# working.net
KiCad netlist of a schematic drawn in EAGLE
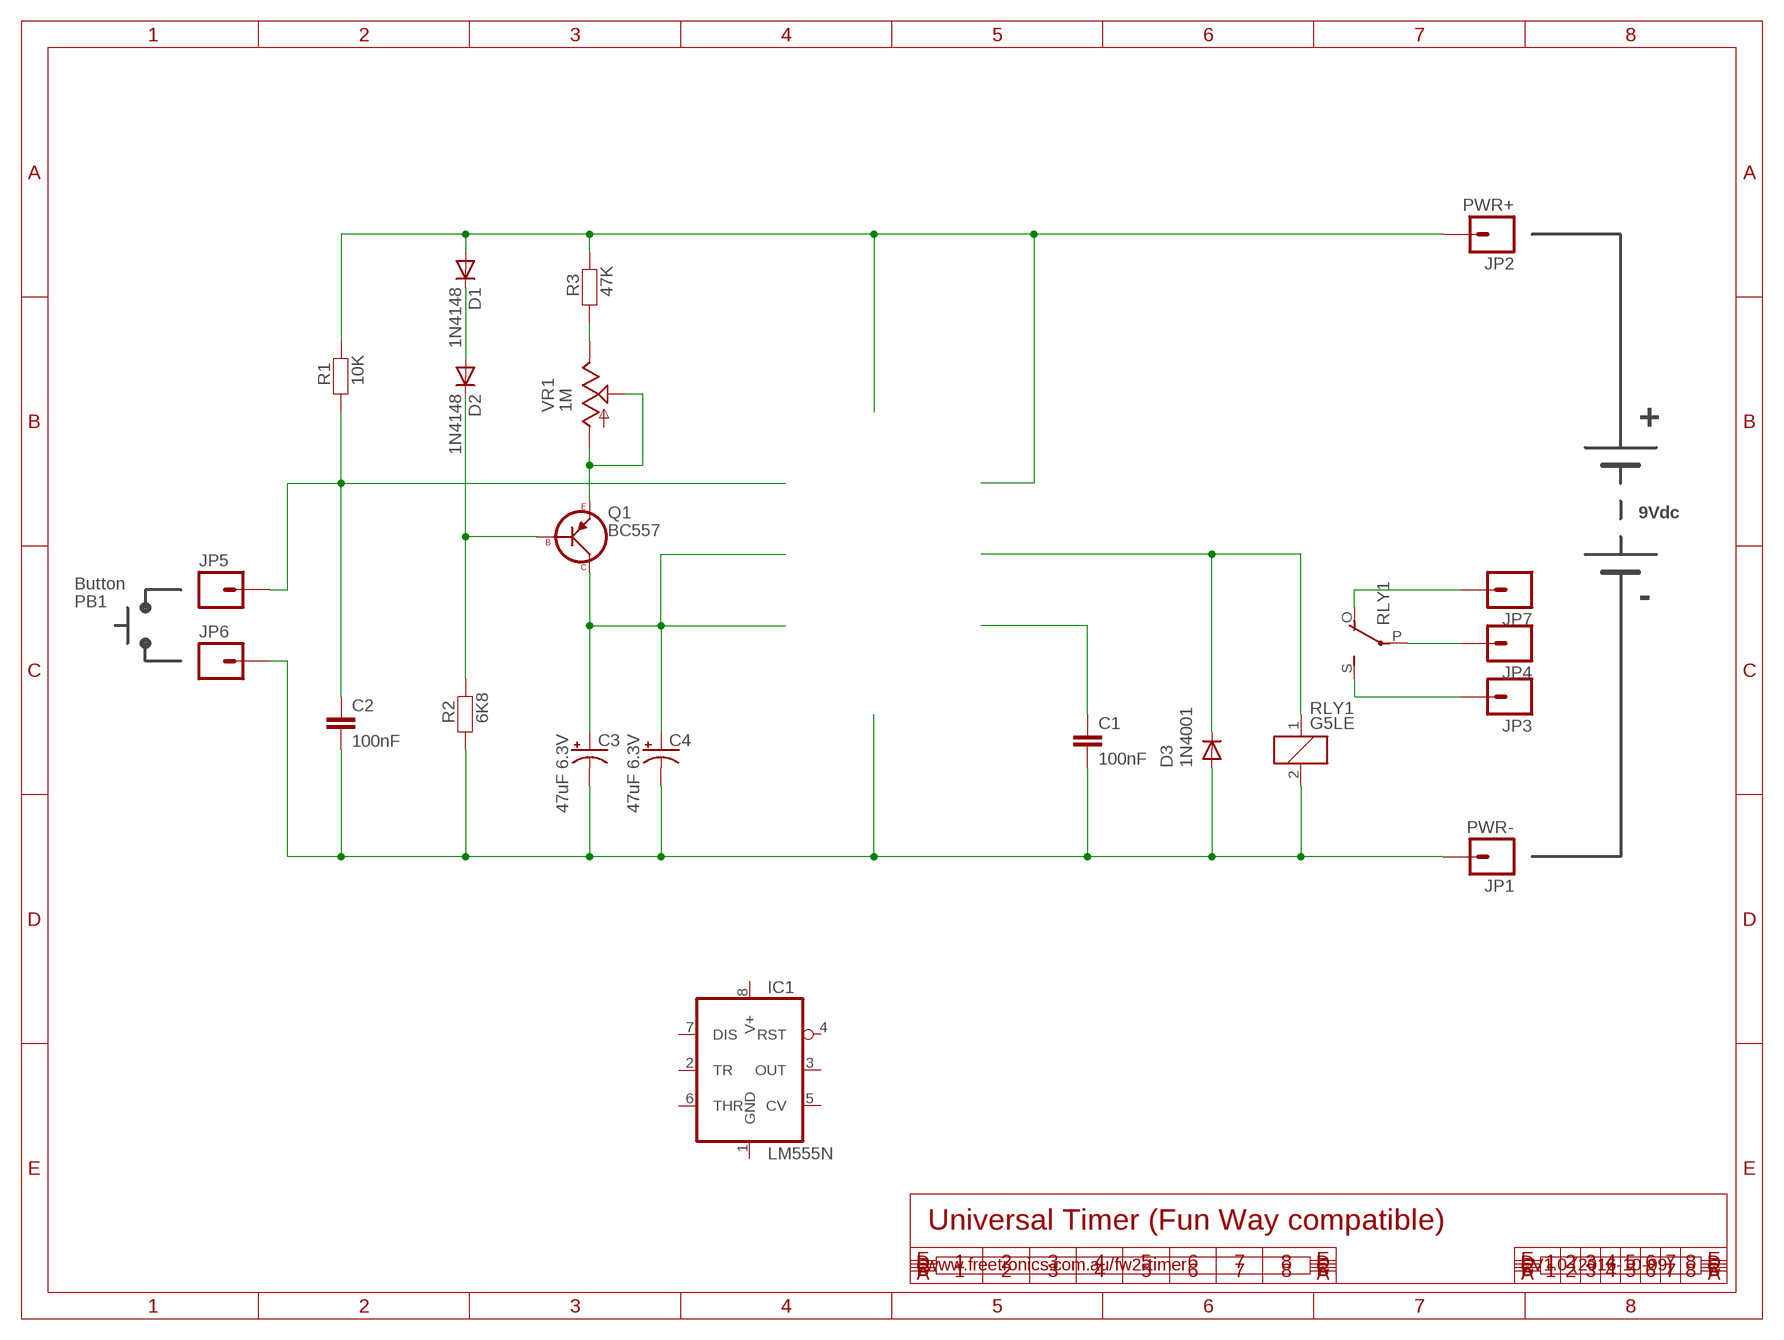
[diagram p0: schematic, sheet 1]

(export (version "E")
  (design (tool "Eeschema 10.0.6"))
  (components
    (comp (ref "C1")
      (value "100nF")
      (footprint "eagle-import:CAP-PTH-SMALL")
      (libsource (lib "eagle-import") (part "CAPPTH"))
    )
    (comp (ref "C2")
      (value "100nF")
      (footprint "eagle-import:CAP-PTH-SMALL")
      (libsource (lib "eagle-import") (part "CAPPTH"))
    )
    (comp (ref "C3")
      (value "47uF 6.3V")
      (footprint "eagle-import:CPOL-RADIAL-10UF-25V")
      (libsource (lib "eagle-import") (part "CAP_POLPTH2"))
    )
    (comp (ref "C4")
      (value "47uF 6.3V")
      (footprint "eagle-import:CPOL-RADIAL-10UF-25V")
      (libsource (lib "eagle-import") (part "CAP_POLPTH2"))
    )
    (comp (ref "D1")
      (value "1N4148")
      (footprint "eagle-import:DIODE-1N914")
      (libsource (lib "eagle-import") (part "DIODE1N914"))
    )
    (comp (ref "D2")
      (value "1N4148")
      (footprint "eagle-import:DIODE-1N914")
      (libsource (lib "eagle-import") (part "DIODE1N914"))
    )
    (comp (ref "D3")
      (value "1N4001")
      (footprint "eagle-import:DIODE-1N4001")
      (libsource (lib "eagle-import") (part "DIODEPTH"))
    )
    (comp (ref "IC1")
      (value "LM555N")
      (footprint "eagle-import:DIL08")
      (libsource (lib "eagle-import") (part "555NLM"))
    )
    (comp (ref "JP1")
      (value "PWR-")
      (footprint "eagle-import:1X01")
      (libsource (lib "eagle-import") (part "M01PTH"))
    )
    (comp (ref "JP2")
      (value "PWR+")
      (footprint "eagle-import:1X01")
      (libsource (lib "eagle-import") (part "M01PTH"))
    )
    (comp (ref "JP3")
      (value "SPKR+")
      (footprint "eagle-import:1X01")
      (libsource (lib "eagle-import") (part "M01PTH"))
    )
    (comp (ref "JP4")
      (value "SPKR-")
      (footprint "eagle-import:1X01")
      (libsource (lib "eagle-import") (part "M01PTH"))
    )
    (comp (ref "JP5")
      (value "PWR-")
      (footprint "eagle-import:1X01")
      (libsource (lib "eagle-import") (part "M01PTH"))
    )
    (comp (ref "JP6")
      (value "PWR-")
      (footprint "eagle-import:1X01")
      (libsource (lib "eagle-import") (part "M01PTH"))
    )
    (comp (ref "JP7")
      (value "SPKR-")
      (footprint "eagle-import:1X01")
      (libsource (lib "eagle-import") (part "M01PTH"))
    )
    (comp (ref "Q1")
      (value "BC557")
      (footprint "eagle-import:TO-92")
      (libsource (lib "eagle-import") (part "BC557"))
    )
    (comp (ref "R1")
      (value "10K")
      (footprint "eagle-import:FREETRONICS_AXIAL-0.4")
      (libsource (lib "eagle-import") (part "FREETRONICS_RESISTORPTH2"))
    )
    (comp (ref "R2")
      (value "6K8")
      (footprint "eagle-import:FREETRONICS_AXIAL-0.4")
      (libsource (lib "eagle-import") (part "FREETRONICS_RESISTORPTH2"))
    )
    (comp (ref "R3")
      (value "47K")
      (footprint "eagle-import:FREETRONICS_AXIAL-0.4")
      (libsource (lib "eagle-import") (part "FREETRONICS_RESISTORPTH2"))
    )
    (comp (ref "RLY1")
      (value "G5LE")
      (footprint "eagle-import:G5LE")
      (libsource (lib "eagle-import") (part "G5LE"))
    )
    (comp (ref "VR1")
      (value "1M")
      (footprint "eagle-import:6MM")
      (libsource (lib "eagle-import") (part "TRIM"))
    )
  )
  (nets
    (net (code "1") (name "/GND") (class "Default")
      (node (ref "IC1") (pin "1") (pinfunction "GND_1") (pintype "power_in"))
    )
    (net (code "2") (name "/V+") (class "Default")
      (node (ref "IC1") (pin "8") (pinfunction "V+_8") (pintype "power_in"))
    )
    (net (code "3") (name "Net-(C3-+)") (class "Default")
      (node (ref "C3") (pin "1") (pinfunction "+_1") (pintype "passive"))
      (node (ref "C4") (pin "1") (pinfunction "+_1") (pintype "passive"))
      (node (ref "Q1") (pin "1") (pinfunction "C_1") (pintype "passive"))
    )
    (net (code "4") (name "Net-(C3--)") (class "Default")
      (node (ref "C1") (pin "2") (pinfunction "2_2") (pintype "passive"))
      (node (ref "C2") (pin "2") (pinfunction "2_2") (pintype "passive"))
      (node (ref "C3") (pin "2") (pinfunction "-_2") (pintype "passive"))
      (node (ref "C4") (pin "2") (pinfunction "-_2") (pintype "passive"))
      (node (ref "D3") (pin "A") (pinfunction "A_A") (pintype "passive"))
      (node (ref "JP1") (pin "1") (pinfunction "1_1") (pintype "passive"))
      (node (ref "JP6") (pin "1") (pinfunction "1_1") (pintype "passive"))
      (node (ref "R2") (pin "P$1") (pinfunction "1_P$1") (pintype "passive"))
      (node (ref "RLY1") (pin "2") (pinfunction "2_2") (pintype "passive"))
    )
    (net (code "5") (name "Net-(D1-PadC)") (class "Default")
      (node (ref "D1") (pin "C") (pinfunction "C_C") (pintype "passive"))
      (node (ref "D2") (pin "A") (pinfunction "A_A") (pintype "passive"))
    )
    (net (code "6") (name "Net-(D3-PadC)") (class "Default")
      (node (ref "D3") (pin "C") (pinfunction "C_C") (pintype "passive"))
      (node (ref "RLY1") (pin "1") (pinfunction "1_1") (pintype "passive"))
    )
    (net (code "7") (name "Net-(JP3-Pad1)") (class "Default")
      (node (ref "JP3") (pin "1") (pinfunction "1_1") (pintype "passive"))
      (node (ref "RLY1") (pin "S") (pinfunction "S_S") (pintype "passive"))
    )
    (net (code "8") (name "Net-(JP4-Pad1)") (class "Default")
      (node (ref "JP4") (pin "1") (pinfunction "1_1") (pintype "passive"))
      (node (ref "RLY1") (pin "P") (pinfunction "P_P") (pintype "passive"))
    )
    (net (code "9") (name "Net-(JP7-Pad1)") (class "Default")
      (node (ref "JP7") (pin "1") (pinfunction "1_1") (pintype "passive"))
      (node (ref "RLY1") (pin "O") (pinfunction "O_O") (pintype "passive"))
    )
    (net (code "10") (name "Net-(Q1-B)") (class "Default")
      (node (ref "D2") (pin "C") (pinfunction "C_C") (pintype "passive"))
      (node (ref "Q1") (pin "2") (pinfunction "B_2") (pintype "passive"))
      (node (ref "R2") (pin "P$2") (pinfunction "2_P$2") (pintype "passive"))
    )
    (net (code "11") (name "Net-(Q1-E)") (class "Default")
      (node (ref "Q1") (pin "3") (pinfunction "E_3") (pintype "passive"))
      (node (ref "VR1") (pin "A") (pinfunction "A_A") (pintype "passive"))
      (node (ref "VR1") (pin "S") (pinfunction "S_S") (pintype "passive"))
    )
    (net (code "12") (name "Net-(R1-1)") (class "Default")
      (node (ref "C2") (pin "1") (pinfunction "1_1") (pintype "passive"))
      (node (ref "JP5") (pin "1") (pinfunction "1_1") (pintype "passive"))
      (node (ref "R1") (pin "P$1") (pinfunction "1_P$1") (pintype "passive"))
    )
    (net (code "13") (name "Net-(R1-2)") (class "Default")
      (node (ref "D1") (pin "A") (pinfunction "A_A") (pintype "passive"))
      (node (ref "JP2") (pin "1") (pinfunction "1_1") (pintype "passive"))
      (node (ref "R1") (pin "P$2") (pinfunction "2_P$2") (pintype "passive"))
      (node (ref "R3") (pin "P$2") (pinfunction "2_P$2") (pintype "passive"))
    )
    (net (code "14") (name "Net-(R3-1)") (class "Default")
      (node (ref "R3") (pin "P$1") (pinfunction "1_P$1") (pintype "passive"))
      (node (ref "VR1") (pin "E") (pinfunction "E_E") (pintype "passive"))
    )
    (net (code "15") (name "unconnected-(C1-Pad1)") (class "Default")
      (node (ref "C1") (pin "1") (pinfunction "1_1") (pintype "passive"))
    )
    (net (code "16") (name "unconnected-(IC1-CV-Pad5)") (class "Default")
      (node (ref "IC1") (pin "5") (pinfunction "CV_5") (pintype "input"))
    )
    (net (code "17") (name "unconnected-(IC1-DIS-Pad7)") (class "Default")
      (node (ref "IC1") (pin "7") (pinfunction "DIS_7") (pintype "input"))
    )
    (net (code "18") (name "unconnected-(IC1-OUT-Pad3)") (class "Default")
      (node (ref "IC1") (pin "3") (pinfunction "OUT_3") (pintype "output"))
    )
    (net (code "19") (name "unconnected-(IC1-RST-Pad4)") (class "Default")
      (node (ref "IC1") (pin "4") (pinfunction "RST_4") (pintype "input"))
    )
    (net (code "20") (name "unconnected-(IC1-THR-Pad6)") (class "Default")
      (node (ref "IC1") (pin "6") (pinfunction "THR_6") (pintype "input"))
    )
    (net (code "21") (name "unconnected-(IC1-TR-Pad2)") (class "Default")
      (node (ref "IC1") (pin "2") (pinfunction "TR_2") (pintype "input"))
    )
  )
)
